# ESP32_wroom_B.net
KiCad netlist of a schematic drawn in EasyEDA Pro
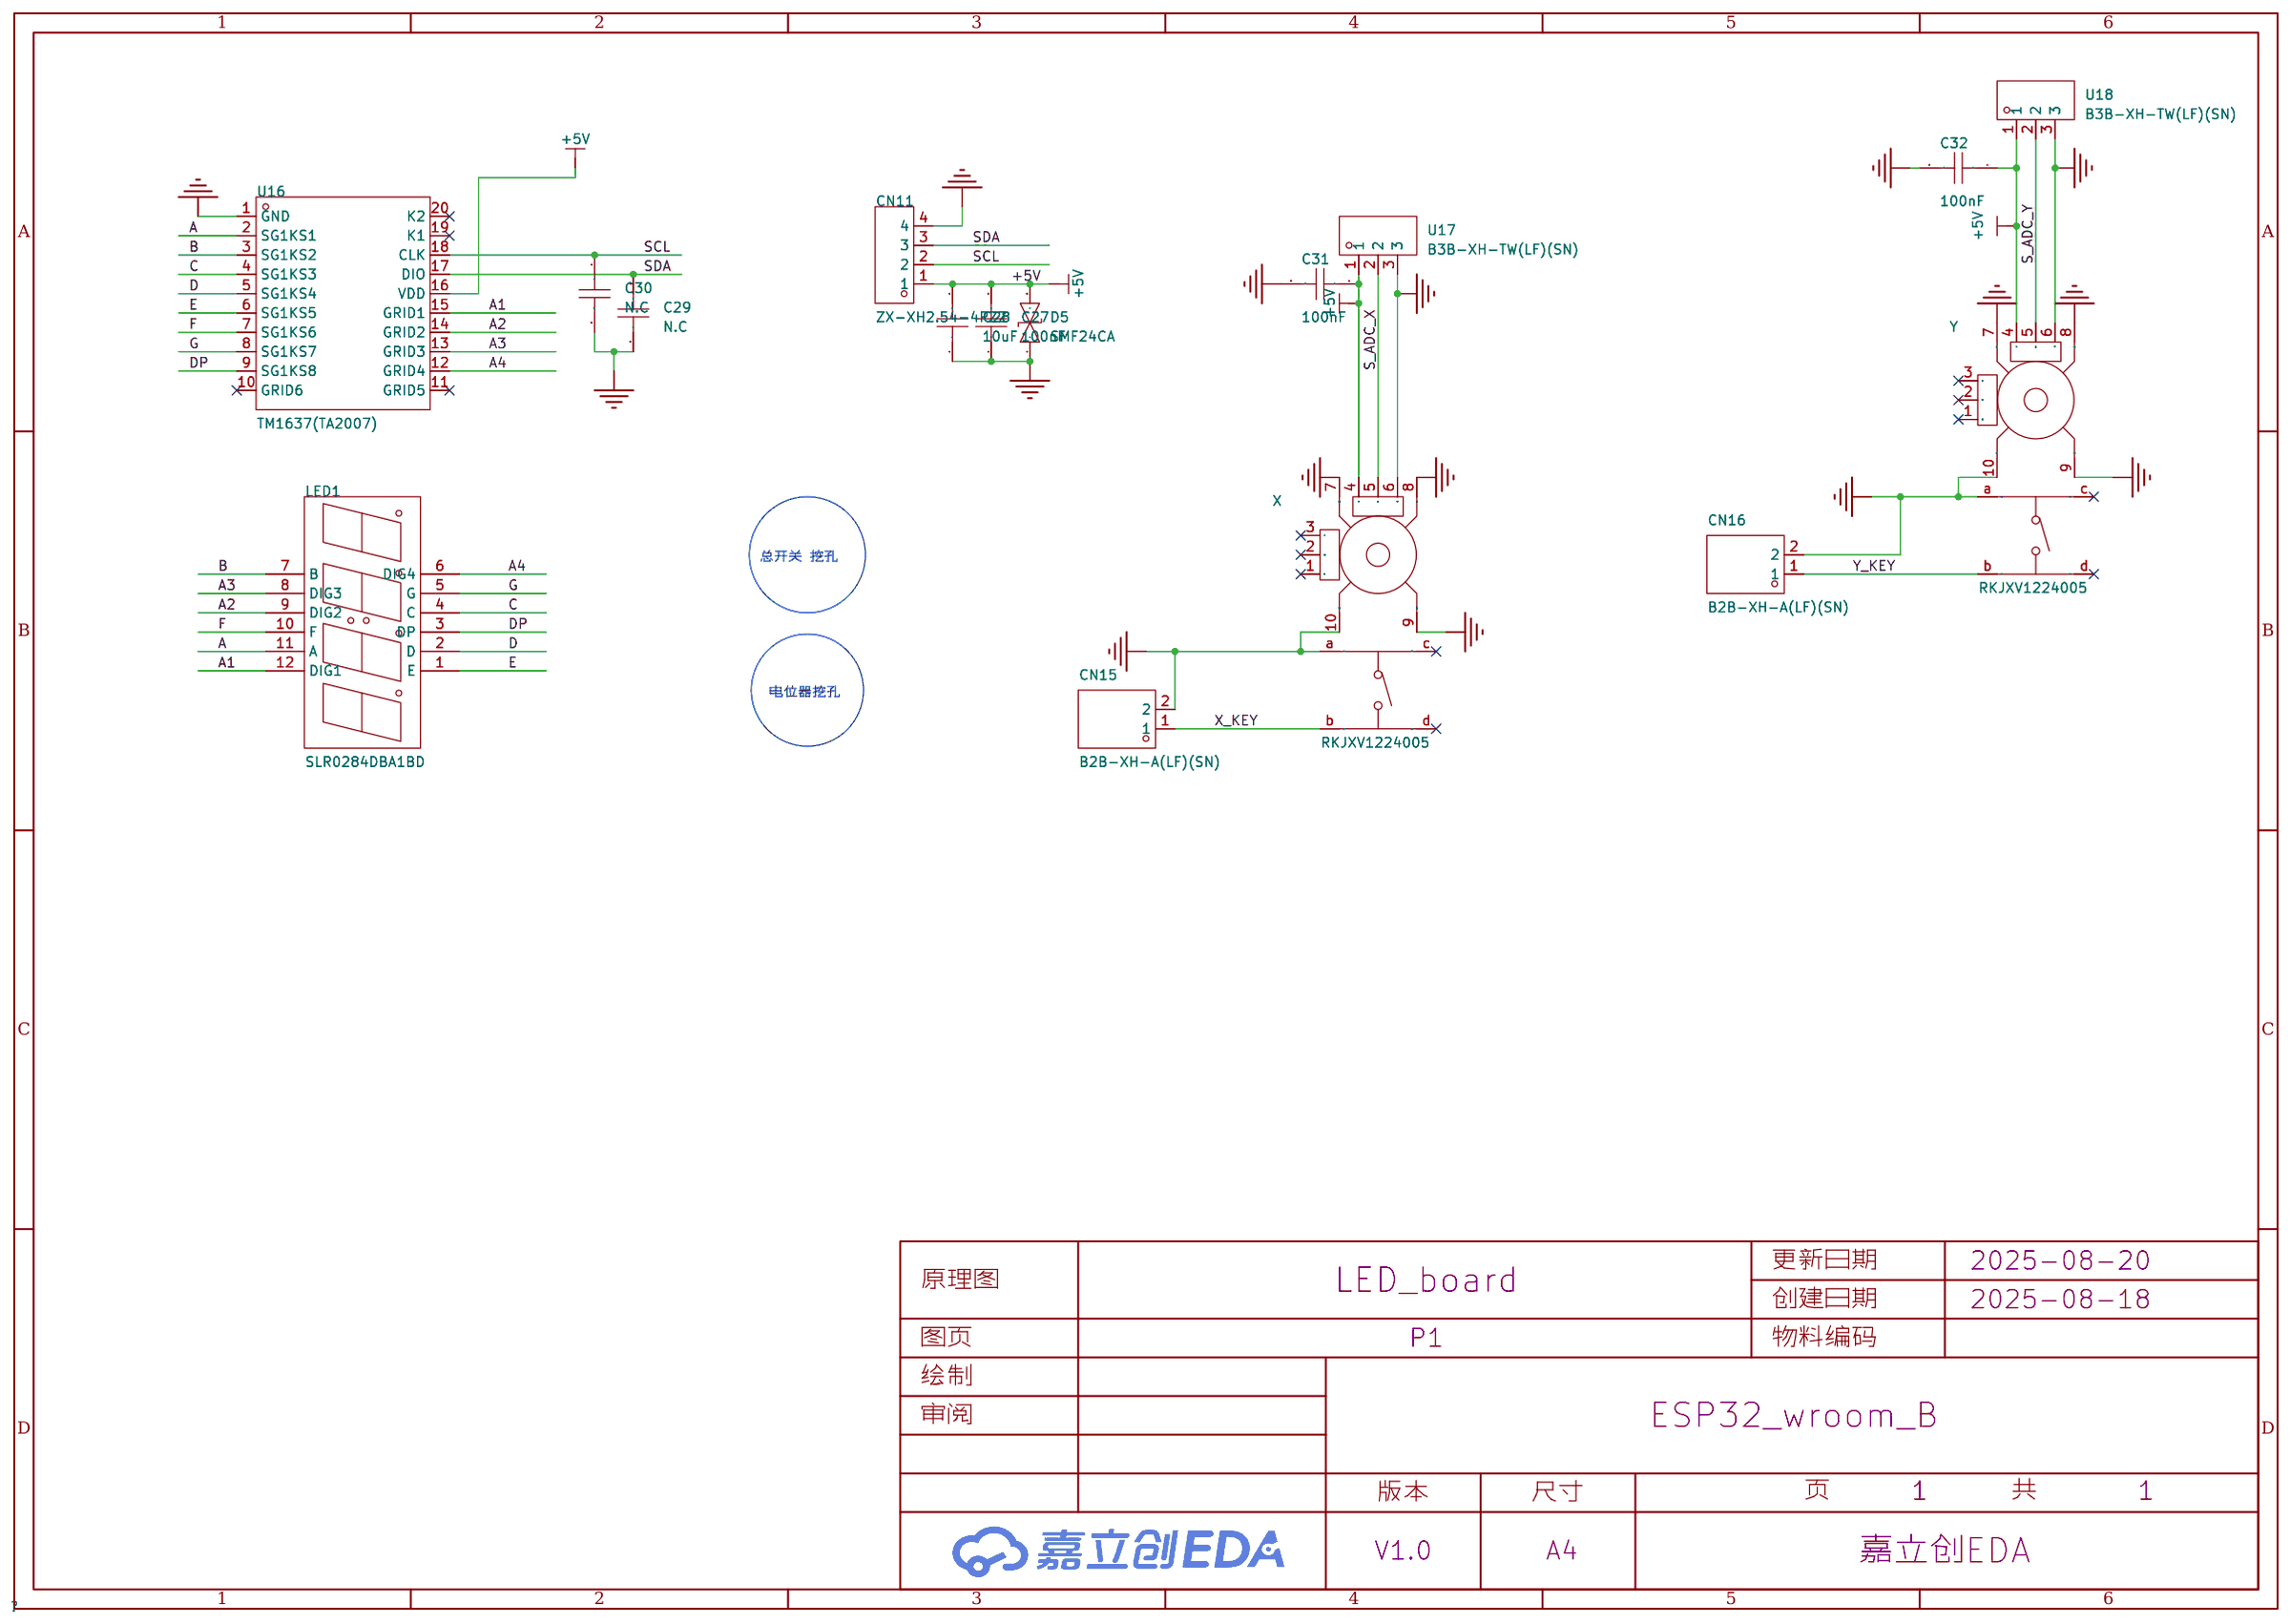
[diagram p0: schematic sheet]

(export (version "E")
  (design (tool "Eeschema 10.0.6"))
  (components
    (comp (ref "C27")
      (value "100nF")
      (footprint "easyedapro:C0603")
      (description "容值:100nF;精度:±10%;额定电压:50V;温度系数:X7R;")
      (fields
        (field (name "Manufacturer Part") "CGA0603X7R104K500JT")
        (field (name "Manufacturer") "HRE(芯声)")
      )
      (libsource (lib "easyedapro") (part "CGA0603X7R104K500JT"))
    )
    (comp (ref "C28")
      (value "10uF")
      (footprint "easyedapro:C0603")
      (description "容值:100nF;精度:±10%;额定电压:50V;温度系数:X7R;")
      (fields
        (field (name "Manufacturer Part") "CGA0603X7R104K500JT")
        (field (name "Manufacturer") "HRE(芯声)")
      )
      (libsource (lib "easyedapro") (part "CGA0603X7R104K500JT"))
    )
    (comp (ref "C29")
      (value "N.C")
      (footprint "easyedapro:C0603")
      (description "容值:100nF;精度:±10%;额定电压:50V;温度系数:X7R;")
      (fields
        (field (name "Manufacturer Part") "CGA0603X7R104K500JT")
        (field (name "Manufacturer") "HRE(芯声)")
      )
      (libsource (lib "easyedapro") (part "CGA0603X7R104K500JT"))
    )
    (comp (ref "C30")
      (value "N.C")
      (footprint "easyedapro:C0603")
      (description "容值:100nF;精度:±10%;额定电压:50V;温度系数:X7R;")
      (fields
        (field (name "Manufacturer Part") "CGA0603X7R104K500JT")
        (field (name "Manufacturer") "HRE(芯声)")
      )
      (libsource (lib "easyedapro") (part "CGA0603X7R104K500JT"))
    )
    (comp (ref "C31")
      (value "100nF")
      (footprint "easyedapro:C0603")
      (description "容值:100nF;精度:±10%;额定电压:50V;温度系数:X7R;")
      (fields
        (field (name "Manufacturer Part") "CGA0603X7R104K500JT")
        (field (name "Manufacturer") "HRE(芯声)")
      )
      (libsource (lib "easyedapro") (part "CGA0603X7R104K500JT"))
    )
    (comp (ref "C32")
      (value "100nF")
      (footprint "easyedapro:C0603")
      (description "容值:100nF;精度:±10%;额定电压:50V;温度系数:X7R;")
      (fields
        (field (name "Manufacturer Part") "CGA0603X7R104K500JT")
        (field (name "Manufacturer") "HRE(芯声)")
      )
      (libsource (lib "easyedapro") (part "CGA0603X7R104K500JT"))
    )
    (comp (ref "CN11")
      (value "ZX-XH2.54-4PZZ")
      (footprint "easyedapro:CONN-TH_4P-P2.50_4PIN")
      (fields (field (name "Manufacturer") "Megastar(兆星)"))
      (libsource (lib "easyedapro") (part "ZX-XH2.54-4PZZ"))
    )
    (comp (ref "CN15")
      (value "B2B-XH-A(LF)(SN)")
      (footprint "easyedapro:CONN-TH_B2B-XH-A-LF-SN")
      (fields (field (name "Manufacturer") "JST"))
      (libsource (lib "easyedapro") (part "B2B-XH-A (LF)(SN)"))
    )
    (comp (ref "CN16")
      (value "B2B-XH-A(LF)(SN)")
      (footprint "easyedapro:CONN-TH_B2B-XH-A-LF-SN")
      (fields (field (name "Manufacturer") "JST"))
      (libsource (lib "easyedapro") (part "B2B-XH-A (LF)(SN)"))
    )
    (comp (ref "D5")
      (value "SMF24CA")
      (footprint "easyedapro:SOD-123FL_L2.7-W1.8-LS3.8-BI")
      (fields (field (name "Manufacturer") "宏迦橙"))
      (libsource (lib "easyedapro") (part "SMF24CA_C19077515"))
    )
    (comp (ref "LED1")
      (value "SLR0284DBA1BD")
      (footprint "easyedapro:LED-SEG-TH_12P-L32.1-W10.0-P2.54-S7.62-BL")
      (fields (field (name "Manufacturer") "SUNLIGHT(光华)"))
      (libsource (lib "easyedapro") (part "SLR0284DBA1BD_C2913024"))
    )
    (comp (ref "U16")
      (value "TM1637(TA2007)")
      (footprint "easyedapro:SOP-20_L12.8-W7.5-P1.27-LS10.4-BL")
      (fields (field (name "Manufacturer") "TM(天微)"))
      (libsource (lib "easyedapro") (part "TM1637(TA2007)"))
    )
    (comp (ref "U17")
      (value "B3B-XH-TW(LF)(SN)")
      (footprint "easyedapro:CONN-TH_B3B-XH-TW-LF-SN")
      (description "插针结构:1x3P;间距:2.5mm;安装方式:-;参考系列:XH;总PIN数:3P;排数:1;每排PIN数:3;行距:-;额定电流:3A;工作温度范围:-25°C~+85°C;")
      (fields (field (name "Manufacturer") "JST"))
      (libsource (lib "easyedapro") (part "B3B-XH-TW(LF)(SN)"))
    )
    (comp (ref "U18")
      (value "B3B-XH-TW(LF)(SN)")
      (footprint "easyedapro:CONN-TH_B3B-XH-TW-LF-SN")
      (description "插针结构:1x3P;间距:2.5mm;安装方式:-;参考系列:XH;总PIN数:3P;排数:1;每排PIN数:3;行距:-;额定电流:3A;工作温度范围:-25°C~+85°C;")
      (fields (field (name "Manufacturer") "JST"))
      (libsource (lib "easyedapro") (part "B3B-XH-TW(LF)(SN)"))
    )
    (comp (ref "X")
      (value "RKJXV1224005")
      (footprint "easyedapro:SW-TH_RKJXV1224005")
      (description "操纵杆复位 中央按动开关 适用于航模玩具遥控器电位器、3D摇杆PS4手柄游戏机、无人机摇杆电位器、工业控制器")
      (fields (field (name "Manufacturer") "ALPSALPINE(阿尔卑斯阿尔派)"))
      (libsource (lib "easyedapro") (part "RKJXV1224005"))
    )
    (comp (ref "Y")
      (value "RKJXV1224005")
      (footprint "easyedapro:SW-TH_RKJXV1224005")
      (description "操纵杆复位 中央按动开关 适用于航模玩具遥控器电位器、3D摇杆PS4手柄游戏机、无人机摇杆电位器、工业控制器")
      (fields (field (name "Manufacturer") "ALPSALPINE(阿尔卑斯阿尔派)"))
      (libsource (lib "easyedapro") (part "RKJXV1224005"))
    )
  )
  (nets
    (net (code "1") (name "+5V") (class "Default")
      (node (ref "C27") (pin "2") (pinfunction "2_2") (pintype "unspecified"))
      (node (ref "C28") (pin "2") (pinfunction "2_2") (pintype "unspecified"))
      (node (ref "C31") (pin "1") (pinfunction "1_1") (pintype "unspecified"))
      (node (ref "C32") (pin "1") (pinfunction "1_1") (pintype "unspecified"))
      (node (ref "CN11") (pin "1") (pinfunction "1_1") (pintype "unspecified"))
      (node (ref "D5") (pin "2") (pinfunction "A_2") (pintype "unspecified"))
      (node (ref "U16") (pin "16") (pinfunction "VDD_16") (pintype "unspecified"))
      (node (ref "U17") (pin "1") (pinfunction "1_1") (pintype "unspecified"))
      (node (ref "U18") (pin "1") (pinfunction "1_1") (pintype "unspecified"))
      (node (ref "X") (pin "4") (pinfunction "A_4") (pintype "unspecified"))
      (node (ref "Y") (pin "4") (pinfunction "A_4") (pintype "unspecified"))
    )
    (net (code "2") (name "/A") (class "Default")
      (node (ref "LED1") (pin "11") (pinfunction "A_11") (pintype "unspecified"))
      (node (ref "U16") (pin "2") (pinfunction "SG1KS1_2") (pintype "unspecified"))
    )
    (net (code "3") (name "/A1") (class "Default")
      (node (ref "LED1") (pin "12") (pinfunction "DIG1_12") (pintype "unspecified"))
      (node (ref "U16") (pin "15") (pinfunction "GRID1_15") (pintype "unspecified"))
    )
    (net (code "4") (name "/A2") (class "Default")
      (node (ref "LED1") (pin "9") (pinfunction "DIG2_9") (pintype "unspecified"))
      (node (ref "U16") (pin "14") (pinfunction "GRID2_14") (pintype "unspecified"))
    )
    (net (code "5") (name "/A3") (class "Default")
      (node (ref "LED1") (pin "8") (pinfunction "DIG3_8") (pintype "unspecified"))
      (node (ref "U16") (pin "13") (pinfunction "GRID3_13") (pintype "unspecified"))
    )
    (net (code "6") (name "/A4") (class "Default")
      (node (ref "LED1") (pin "6") (pinfunction "DIG4_6") (pintype "unspecified"))
      (node (ref "U16") (pin "12") (pinfunction "GRID4_12") (pintype "unspecified"))
    )
    (net (code "7") (name "/B") (class "Default")
      (node (ref "LED1") (pin "7") (pinfunction "B_7") (pintype "unspecified"))
      (node (ref "U16") (pin "3") (pinfunction "SG1KS2_3") (pintype "unspecified"))
    )
    (net (code "8") (name "/C") (class "Default")
      (node (ref "LED1") (pin "4") (pinfunction "C_4") (pintype "unspecified"))
      (node (ref "U16") (pin "4") (pinfunction "SG1KS3_4") (pintype "unspecified"))
    )
    (net (code "9") (name "/D") (class "Default")
      (node (ref "LED1") (pin "2") (pinfunction "D_2") (pintype "unspecified"))
      (node (ref "U16") (pin "5") (pinfunction "SG1KS4_5") (pintype "unspecified"))
    )
    (net (code "10") (name "/DP") (class "Default")
      (node (ref "LED1") (pin "3") (pinfunction "DP_3") (pintype "unspecified"))
      (node (ref "U16") (pin "9") (pinfunction "SG1KS8_9") (pintype "unspecified"))
    )
    (net (code "11") (name "/E") (class "Default")
      (node (ref "LED1") (pin "1") (pinfunction "E_1") (pintype "unspecified"))
      (node (ref "U16") (pin "6") (pinfunction "SG1KS5_6") (pintype "unspecified"))
    )
    (net (code "12") (name "/F") (class "Default")
      (node (ref "LED1") (pin "10") (pinfunction "F_10") (pintype "unspecified"))
      (node (ref "U16") (pin "7") (pinfunction "SG1KS6_7") (pintype "unspecified"))
    )
    (net (code "13") (name "/G") (class "Default")
      (node (ref "LED1") (pin "5") (pinfunction "G_5") (pintype "unspecified"))
      (node (ref "U16") (pin "8") (pinfunction "SG1KS7_8") (pintype "unspecified"))
    )
    (net (code "14") (name "/SCL") (class "Default")
      (node (ref "C30") (pin "1") (pinfunction "1_1") (pintype "unspecified"))
      (node (ref "CN11") (pin "2") (pinfunction "2_2") (pintype "unspecified"))
      (node (ref "U16") (pin "18") (pinfunction "CLK_18") (pintype "unspecified"))
    )
    (net (code "15") (name "/SDA") (class "Default")
      (node (ref "C29") (pin "1") (pinfunction "1_1") (pintype "unspecified"))
      (node (ref "CN11") (pin "3") (pinfunction "3_3") (pintype "unspecified"))
      (node (ref "U16") (pin "17") (pinfunction "DIO_17") (pintype "unspecified"))
    )
    (net (code "16") (name "/S_ADC_X") (class "Default")
      (node (ref "U17") (pin "2") (pinfunction "2_2") (pintype "unspecified"))
      (node (ref "X") (pin "5") (pinfunction "DTA_5") (pintype "unspecified"))
    )
    (net (code "17") (name "/S_ADC_Y") (class "Default")
      (node (ref "U18") (pin "2") (pinfunction "2_2") (pintype "unspecified"))
      (node (ref "Y") (pin "5") (pinfunction "DTA_5") (pintype "unspecified"))
    )
    (net (code "18") (name "/X_KEY") (class "Default")
      (node (ref "CN15") (pin "1") (pinfunction "1_1") (pintype "unspecified"))
      (node (ref "X") (pin "b") (pinfunction "b_b") (pintype "unspecified"))
    )
    (net (code "19") (name "/Y_KEY") (class "Default")
      (node (ref "CN16") (pin "1") (pinfunction "1_1") (pintype "unspecified"))
      (node (ref "Y") (pin "b") (pinfunction "b_b") (pintype "unspecified"))
    )
    (net (code "20") (name "GND") (class "Default")
      (node (ref "C27") (pin "1") (pinfunction "1_1") (pintype "unspecified"))
      (node (ref "C28") (pin "1") (pinfunction "1_1") (pintype "unspecified"))
      (node (ref "C29") (pin "2") (pinfunction "2_2") (pintype "unspecified"))
      (node (ref "C30") (pin "2") (pinfunction "2_2") (pintype "unspecified"))
      (node (ref "C31") (pin "2") (pinfunction "2_2") (pintype "unspecified"))
      (node (ref "C32") (pin "2") (pinfunction "2_2") (pintype "unspecified"))
      (node (ref "CN11") (pin "4") (pinfunction "4_4") (pintype "unspecified"))
      (node (ref "CN15") (pin "2") (pinfunction "2_2") (pintype "unspecified"))
      (node (ref "CN16") (pin "2") (pinfunction "2_2") (pintype "unspecified"))
      (node (ref "D5") (pin "1") (pinfunction "K_1") (pintype "unspecified"))
      (node (ref "U16") (pin "1") (pinfunction "GND_1") (pintype "unspecified"))
      (node (ref "U17") (pin "3") (pinfunction "3_3") (pintype "unspecified"))
      (node (ref "U18") (pin "3") (pinfunction "3_3") (pintype "unspecified"))
      (node (ref "X") (pin "10") (pinfunction "GND_10") (pintype "unspecified"))
      (node (ref "X") (pin "6") (pinfunction "B_6") (pintype "unspecified"))
      (node (ref "X") (pin "7") (pinfunction "GND_7") (pintype "unspecified"))
      (node (ref "X") (pin "8") (pinfunction "GND_8") (pintype "unspecified"))
      (node (ref "X") (pin "9") (pinfunction "GND_9") (pintype "unspecified"))
      (node (ref "X") (pin "a") (pinfunction "a_a") (pintype "unspecified"))
      (node (ref "Y") (pin "10") (pinfunction "GND_10") (pintype "unspecified"))
      (node (ref "Y") (pin "6") (pinfunction "B_6") (pintype "unspecified"))
      (node (ref "Y") (pin "7") (pinfunction "GND_7") (pintype "unspecified"))
      (node (ref "Y") (pin "8") (pinfunction "GND_8") (pintype "unspecified"))
      (node (ref "Y") (pin "9") (pinfunction "GND_9") (pintype "unspecified"))
      (node (ref "Y") (pin "a") (pinfunction "a_a") (pintype "unspecified"))
    )
    (net (code "21") (name "unconnected-(U16-GRID5-Pad11)") (class "Default")
      (node (ref "U16") (pin "11") (pinfunction "GRID5_11") (pintype "unspecified+no_connect"))
    )
    (net (code "22") (name "unconnected-(U16-GRID6-Pad10)") (class "Default")
      (node (ref "U16") (pin "10") (pinfunction "GRID6_10") (pintype "unspecified+no_connect"))
    )
    (net (code "23") (name "unconnected-(U16-K1-Pad19)") (class "Default")
      (node (ref "U16") (pin "19") (pinfunction "K1_19") (pintype "unspecified+no_connect"))
    )
    (net (code "24") (name "unconnected-(U16-K2-Pad20)") (class "Default")
      (node (ref "U16") (pin "20") (pinfunction "K2_20") (pintype "unspecified+no_connect"))
    )
    (net (code "25") (name "unconnected-(X-A-Pad3)") (class "Default")
      (node (ref "X") (pin "3") (pinfunction "A_3") (pintype "unspecified+no_connect"))
    )
    (net (code "26") (name "unconnected-(X-B-Pad1)") (class "Default")
      (node (ref "X") (pin "1") (pinfunction "B_1") (pintype "unspecified+no_connect"))
    )
    (net (code "27") (name "unconnected-(X-DTA-Pad2)") (class "Default")
      (node (ref "X") (pin "2") (pinfunction "DTA_2") (pintype "unspecified+no_connect"))
    )
    (net (code "28") (name "unconnected-(X-Padc)") (class "Default")
      (node (ref "X") (pin "c") (pinfunction "c_c") (pintype "unspecified+no_connect"))
    )
    (net (code "29") (name "unconnected-(X-Padd)") (class "Default")
      (node (ref "X") (pin "d") (pinfunction "d_d") (pintype "unspecified+no_connect"))
    )
    (net (code "30") (name "unconnected-(Y-A-Pad3)") (class "Default")
      (node (ref "Y") (pin "3") (pinfunction "A_3") (pintype "unspecified+no_connect"))
    )
    (net (code "31") (name "unconnected-(Y-B-Pad1)") (class "Default")
      (node (ref "Y") (pin "1") (pinfunction "B_1") (pintype "unspecified+no_connect"))
    )
    (net (code "32") (name "unconnected-(Y-DTA-Pad2)") (class "Default")
      (node (ref "Y") (pin "2") (pinfunction "DTA_2") (pintype "unspecified+no_connect"))
    )
    (net (code "33") (name "unconnected-(Y-Padc)") (class "Default")
      (node (ref "Y") (pin "c") (pinfunction "c_c") (pintype "unspecified+no_connect"))
    )
    (net (code "34") (name "unconnected-(Y-Padd)") (class "Default")
      (node (ref "Y") (pin "d") (pinfunction "d_d") (pintype "unspecified+no_connect"))
    )
  )
)
